# STO.net
KiCad netlist of a schematic drawn in Altium Designer
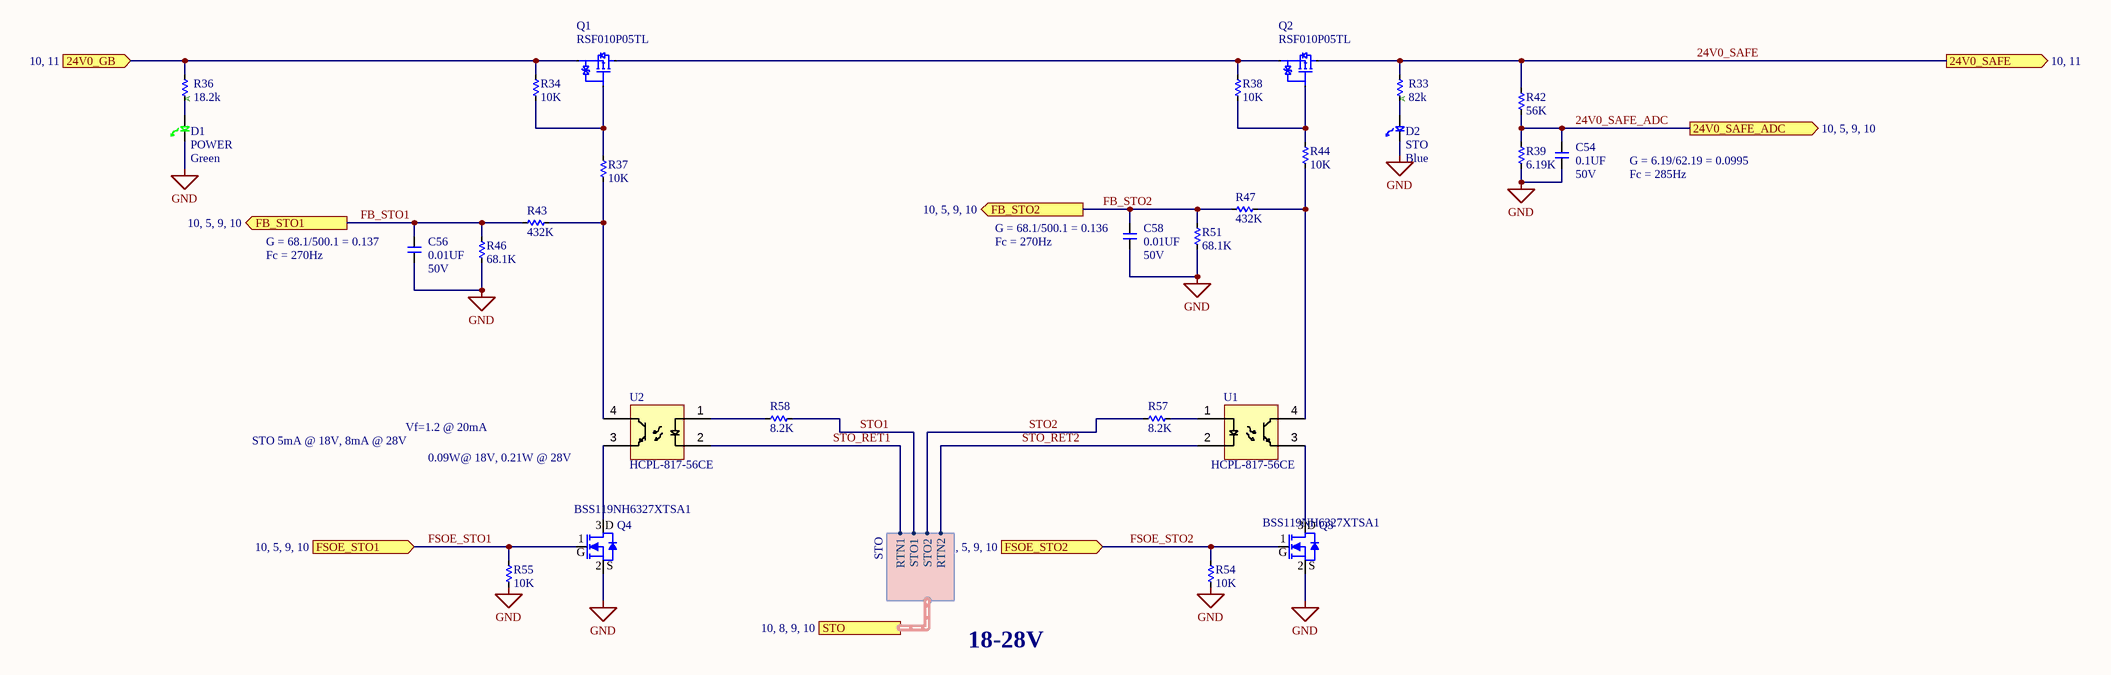
[diagram p0: STO.SchDoc]

(export (version "E")
  (design (tool "Eeschema 10.0.6"))
  (components
    (comp (ref "C54")
      (value "0.1UF")
      (footprint "C0402")
      (description "CAP, CER, X5R, 0.1uF, 10%, 50V, 0402, 0.55mm")
      (fields
        (field (name "MFG") "YAGEO")
        (field (name "VOLTAGE") "50V")
        (field (name "Comment") "__Template_Cap")
      )
      (libsource (lib "AltiumReleaseLibDB") (part "__Template_Cap"))
    )
    (comp (ref "C56")
      (value "0.01UF")
      (footprint "C0402")
      (description "CAP, CER, X7R, 0.01uF, 50V, 20%, 0402, 0.56mm T")
      (fields
        (field (name "MFG") "KEMET")
        (field (name "VOLTAGE") "50V")
        (field (name "Comment") "__Template_Cap")
      )
      (libsource (lib "AltiumReleaseLibDB") (part "__Template_Cap"))
    )
    (comp (ref "C58")
      (value "0.01UF")
      (footprint "C0402")
      (description "CAP, CER, X7R, 0.01uF, 50V, 20%, 0402, 0.56mm T")
      (fields
        (field (name "MFG") "KEMET")
        (field (name "VOLTAGE") "50V")
        (field (name "Comment") "__Template_Cap")
      )
      (libsource (lib "AltiumReleaseLibDB") (part "__Template_Cap"))
    )
    (comp (ref "D1")
      (value "POWER")
      (footprint "LEDSC160X80X90L40-GREEN")
      (description "LED, GREEN, 569nm, 30mA, CLEAR, 0603")
      (fields (field (name "ALTIUM_VALUE") "Green") (field (name "MFG") "Lite-On Inc."))
      (libsource (lib "Components") (part "LED-GREEN"))
    )
    (comp (ref "D2")
      (value "STO")
      (footprint "LEDSC160X80X90L40-BLUE")
      (description "LED, BLUE, 470nm, 15mA, DIFFUSED, 0603")
      (fields (field (name "ALTIUM_VALUE") "Blue") (field (name "MFG") "OSRAM Opto (ams OSRAM)"))
      (libsource (lib "Components") (part "LED-BLUE"))
    )
    (comp (ref "Q1")
      (value "PFET_RSF010P05TL")
      (footprint "TUMT3")
      (description "MOSFET, PWR, P-CH, 45VDS, 1A ID, 460mOhm@ 1A, SMD-3")
      (fields (field (name "MFG") "Rohm Semiconductor") (field (name "MFG P/N") "RSF010P05TL"))
      (libsource (lib "AltiumReleaseLibDB") (part "PFET_RSF010P05TL"))
    )
    (comp (ref "Q2")
      (value "PFET_RSF010P05TL")
      (footprint "TUMT3")
      (description "MOSFET, PWR, P-CH, 45VDS, 1A ID, 460mOhm@ 1A, SMD-3")
      (fields (field (name "MFG") "Rohm Semiconductor") (field (name "MFG P/N") "RSF010P05TL"))
      (libsource (lib "AltiumReleaseLibDB") (part "PFET_RSF010P05TL"))
    )
    (comp (ref "Q3")
      (value "BSS119NH6327XTSA1")
      (footprint "SOT23-3P95_240X110L43N")
      (description "XSTR, MOSFET, ENHANCEMENT MODE, N-CH, 100V, 0.17A, SOT23-3")
      (fields (field (name "MFG") "onsemi") (field (name "Comment") "ONSEMI BSS123"))
      (libsource (lib "Components") (part "NFET-GSD"))
    )
    (comp (ref "Q4")
      (value "BSS119NH6327XTSA1")
      (footprint "SOT23-3P95_240X110L43N")
      (description "XSTR, MOSFET, ENHANCEMENT MODE, N-CH, 100V, 0.17A, SOT23-3")
      (fields (field (name "MFG") "onsemi") (field (name "Comment") "ONSEMI BSS123"))
      (libsource (lib "Components") (part "NFET-GSD"))
    )
    (comp (ref "R33")
      (value "82k")
      (footprint "R0402")
      (description "Res, 82k, +/-1%, 0.1W, 0402, AUTO GRADE")
      (fields
        (field (name "MFG") "Panasonic Electronic Components")
        (field (name "Comment") "PANASONIC ERJ2RKF8202X")
      )
      (libsource (lib "Components") (part "RES-AUTO"))
    )
    (comp (ref "R34")
      (value "10K")
      (footprint "R0402")
      (description "RES, 10K, 1%, 1/10W, 0402, AUTOGRADE")
      (fields (field (name "MFG") "PANASONIC"))
      (libsource (lib "AltiumReleaseLibDB") (part "__Template_Resistor"))
    )
    (comp (ref "R36")
      (value "18.2k")
      (footprint "R0402")
      (description "Res, 18.2k, +/-1%, 0.1W, 0402, AUTO GRADE")
      (fields
        (field (name "MFG") "Panasonic Electronic Components")
        (field (name "Comment") "PANASONIC ERJ2RKF1822X")
      )
      (libsource (lib "Components") (part "RES-AUTO"))
    )
    (comp (ref "R37")
      (value "10K")
      (footprint "R0402")
      (description "RES, 10K, 1%, 1/10W, 0402, AUTOGRADE")
      (fields (field (name "MFG") "PANASONIC"))
      (libsource (lib "AltiumReleaseLibDB") (part "__Template_Resistor"))
    )
    (comp (ref "R38")
      (value "10K")
      (footprint "R0402")
      (description "RES, 10K, 1%, 1/10W, 0402, AUTOGRADE")
      (fields (field (name "MFG") "PANASONIC"))
      (libsource (lib "AltiumReleaseLibDB") (part "__Template_Resistor"))
    )
    (comp (ref "R39")
      (value "6.19K")
      (footprint "R0402")
      (description "RES, 6.19K, 1%, 1/16W, 0402")
      (fields (field (name "MFG") "Yageo"))
      (libsource (lib "AltiumReleaseLibDB") (part "__Template_Resistor"))
    )
    (comp (ref "R42")
      (value "56K")
      (footprint "R0402")
      (description "RES, 56K, 1%, 1/16W, 0402")
      (fields (field (name "MFG") "VISHAY"))
      (libsource (lib "AltiumReleaseLibDB") (part "__Template_Resistor"))
    )
    (comp (ref "R43")
      (value "432K")
      (footprint "R0402")
      (description "RES, 432K, 1%, 1/16W, 0402")
      (fields (field (name "MFG") "VISHAY"))
      (libsource (lib "AltiumReleaseLibDB") (part "__Template_Resistor"))
    )
    (comp (ref "R44")
      (value "10K")
      (footprint "R0402")
      (description "RES, 10K, 1%, 1/10W, 0402, AUTOGRADE")
      (fields (field (name "MFG") "PANASONIC"))
      (libsource (lib "AltiumReleaseLibDB") (part "__Template_Resistor"))
    )
    (comp (ref "R46")
      (value "68.1K")
      (footprint "R0402")
      (description "RES, 68.1K, 1%, 1/16W, 0402")
      (fields (field (name "MFG") "Stackpole Electronics Inc"))
      (libsource (lib "AltiumReleaseLibDB") (part "__Template_Resistor"))
    )
    (comp (ref "R47")
      (value "432K")
      (footprint "R0402")
      (description "RES, 432K, 1%, 1/16W, 0402")
      (fields (field (name "MFG") "VISHAY"))
      (libsource (lib "AltiumReleaseLibDB") (part "__Template_Resistor"))
    )
    (comp (ref "R51")
      (value "68.1K")
      (footprint "R0402")
      (description "RES, 68.1K, 1%, 1/16W, 0402")
      (fields (field (name "MFG") "Stackpole Electronics Inc"))
      (libsource (lib "AltiumReleaseLibDB") (part "__Template_Resistor"))
    )
    (comp (ref "R54")
      (value "10K")
      (footprint "R0402")
      (description "RES, 10K, 1%, 1/10W, 0402, AUTOGRADE")
      (fields (field (name "MFG") "PANASONIC"))
      (libsource (lib "AltiumReleaseLibDB") (part "__Template_Resistor"))
    )
    (comp (ref "R55")
      (value "10K")
      (footprint "R0402")
      (description "RES, 10K, 1%, 1/10W, 0402, AUTOGRADE")
      (fields (field (name "MFG") "PANASONIC"))
      (libsource (lib "AltiumReleaseLibDB") (part "__Template_Resistor"))
    )
    (comp (ref "R57")
      (value "8.2K")
      (footprint "R1206")
      (description "RES 8.2K OHM 1% 1/4W 1206")
      (fields (field (name "MFG") "STACKPOLE ELECTRONICS"))
      (libsource (lib "AltiumReleaseLibDB") (part "__Template_Resistor"))
    )
    (comp (ref "R58")
      (value "8.2K")
      (footprint "R1206")
      (description "RES 8.2K OHM 1% 1/4W 1206")
      (fields (field (name "MFG") "STACKPOLE ELECTRONICS"))
      (libsource (lib "AltiumReleaseLibDB") (part "__Template_Resistor"))
    )
    (comp (ref "U1")
      (value "OPTO_HCPL-817-56CE")
      (footprint "OPTO_HCPL-817-56CE")
      (description "ISOLATOR, OPTOISOLATOR, PHOTO TRANSISTOR, 70V, 50mA, SMD-4")
      (fields (field (name "MFG") "Broadcom Limited") (field (name "MFG P/N") "HCPL-817-56CE"))
      (libsource (lib "AltiumReleaseLibDB") (part "OPTO_HCPL-817-56CE"))
    )
    (comp (ref "U2")
      (value "OPTO_HCPL-817-56CE")
      (footprint "OPTO_HCPL-817-56CE")
      (description "ISOLATOR, OPTOISOLATOR, PHOTO TRANSISTOR, 70V, 50mA, SMD-4")
      (fields (field (name "MFG") "Broadcom Limited") (field (name "MFG P/N") "HCPL-817-56CE"))
      (libsource (lib "") (part "OPTO_HCPL-817-56CE_1"))
    )
  )
  (nets
    (net (code "2") (name "/24V0_GB") (class "Default")
      (node (ref "Q1") (pin "S") (pinfunction "S_S") (pintype "passive"))
      (node (ref "R34") (pin "2") (pintype "passive"))
      (node (ref "R36") (pin "2") (pintype "passive"))
    )
    (net (code "3") (name "/24V0_SAFE") (class "Default")
      (node (ref "Q2") (pin "D") (pinfunction "D_D") (pintype "passive"))
      (node (ref "R33") (pin "2") (pintype "passive"))
      (node (ref "R42") (pin "2") (pintype "passive"))
    )
    (net (code "4") (name "/24V0_SAFE_ADC") (class "Default")
      (node (ref "C54") (pin "1") (pintype "passive"))
      (node (ref "R39") (pin "2") (pintype "passive"))
      (node (ref "R42") (pin "1") (pintype "passive"))
    )
    (net (code "5") (name "/FB_STO1") (class "Default")
      (node (ref "C56") (pin "1") (pintype "passive"))
      (node (ref "R43") (pin "1") (pintype "passive"))
      (node (ref "R46") (pin "2") (pintype "passive"))
    )
    (net (code "6") (name "/FB_STO2") (class "Default")
      (node (ref "C58") (pin "1") (pintype "passive"))
      (node (ref "R47") (pin "1") (pintype "passive"))
      (node (ref "R51") (pin "2") (pintype "passive"))
    )
    (net (code "7") (name "/FSOE_STO1") (class "Default")
      (node (ref "Q4") (pin "1") (pinfunction "G_1") (pintype "passive"))
      (node (ref "R55") (pin "2") (pintype "passive"))
    )
    (net (code "8") (name "/FSOE_STO2") (class "Default")
      (node (ref "Q3") (pin "1") (pinfunction "G_1") (pintype "passive"))
      (node (ref "R54") (pin "2") (pintype "passive"))
    )
    (net (code "9") (name "/STO1") (class "Default") (node (ref "R58") (pin "2") (pintype "passive")))
    (net (code "10") (name "/STO2") (class "Default") (node (ref "R57") (pin "1") (pintype "passive")))
    (net (code "11") (name "/STO_RET1") (class "Default")
      (node (ref "U2") (pin "2") (pinfunction "Cathode_2") (pintype "passive"))
    )
    (net (code "12") (name "/STO_RET2") (class "Default")
      (node (ref "U1") (pin "2") (pinfunction "Cathode_2") (pintype "passive"))
    )
    (net (code "14") (name "GND") (class "Default")
      (node (ref "C54") (pin "2") (pintype "passive"))
      (node (ref "C56") (pin "2") (pintype "passive"))
      (node (ref "C58") (pin "2") (pintype "passive"))
      (node (ref "D1") (pin "1") (pinfunction "CATHODE_1") (pintype "passive"))
      (node (ref "D2") (pin "1") (pinfunction "CATHODE_1") (pintype "passive"))
      (node (ref "Q3") (pin "2") (pinfunction "S_2") (pintype "passive"))
      (node (ref "Q4") (pin "2") (pinfunction "S_2") (pintype "passive"))
      (node (ref "R39") (pin "1") (pintype "passive"))
      (node (ref "R46") (pin "1") (pintype "passive"))
      (node (ref "R51") (pin "1") (pintype "passive"))
      (node (ref "R54") (pin "1") (pintype "passive"))
      (node (ref "R55") (pin "1") (pintype "passive"))
    )
    (net (code "15") (name "Net-(D1-ANODE)") (class "Default")
      (node (ref "D1") (pin "2") (pinfunction "ANODE_2") (pintype "passive"))
      (node (ref "R36") (pin "1") (pintype "passive"))
    )
    (net (code "16") (name "Net-(D2-ANODE)") (class "Default")
      (node (ref "D2") (pin "2") (pinfunction "ANODE_2") (pintype "passive"))
      (node (ref "R33") (pin "1") (pintype "passive"))
    )
    (net (code "17") (name "Net-(Q1-PadD)") (class "Default")
      (node (ref "Q1") (pin "D") (pinfunction "D_D") (pintype "passive"))
      (node (ref "Q2") (pin "S") (pinfunction "S_S") (pintype "passive"))
      (node (ref "R38") (pin "2") (pintype "passive"))
    )
    (net (code "18") (name "Net-(Q1-PadG)") (class "Default")
      (node (ref "Q1") (pin "G") (pinfunction "G_G") (pintype "passive"))
      (node (ref "R34") (pin "1") (pintype "passive"))
      (node (ref "R37") (pin "2") (pintype "passive"))
    )
    (net (code "19") (name "Net-(Q2-PadG)") (class "Default")
      (node (ref "Q2") (pin "G") (pinfunction "G_G") (pintype "passive"))
      (node (ref "R38") (pin "1") (pintype "passive"))
      (node (ref "R44") (pin "2") (pintype "passive"))
    )
    (net (code "20") (name "Net-(Q3-D)") (class "Default")
      (node (ref "Q3") (pin "3") (pinfunction "D_3") (pintype "passive"))
      (node (ref "U1") (pin "3") (pinfunction "Emitter_3") (pintype "passive"))
    )
    (net (code "21") (name "Net-(Q4-D)") (class "Default")
      (node (ref "Q4") (pin "3") (pinfunction "D_3") (pintype "passive"))
      (node (ref "U2") (pin "3") (pinfunction "Emitter_3") (pintype "passive"))
    )
    (net (code "22") (name "Net-(U1-Anode)") (class "Default")
      (node (ref "R57") (pin "2") (pintype "passive"))
      (node (ref "U1") (pin "1") (pinfunction "Anode_1") (pintype "passive"))
    )
    (net (code "23") (name "Net-(U1-Collector)") (class "Default")
      (node (ref "R44") (pin "1") (pintype "passive"))
      (node (ref "R47") (pin "2") (pintype "passive"))
      (node (ref "U1") (pin "4") (pinfunction "Collector_4") (pintype "passive"))
    )
    (net (code "24") (name "Net-(U2-Anode)") (class "Default")
      (node (ref "R58") (pin "1") (pintype "passive"))
      (node (ref "U2") (pin "1") (pinfunction "Anode_1") (pintype "passive"))
    )
    (net (code "25") (name "Net-(U2-Collector)") (class "Default")
      (node (ref "R37") (pin "1") (pintype "passive"))
      (node (ref "R43") (pin "2") (pintype "passive"))
      (node (ref "U2") (pin "4") (pinfunction "Collector_4") (pintype "passive"))
    )
  )
)
